# 15_-_PWR_3V3_1V375.net
KiCad netlist of a schematic drawn in Altium Designer
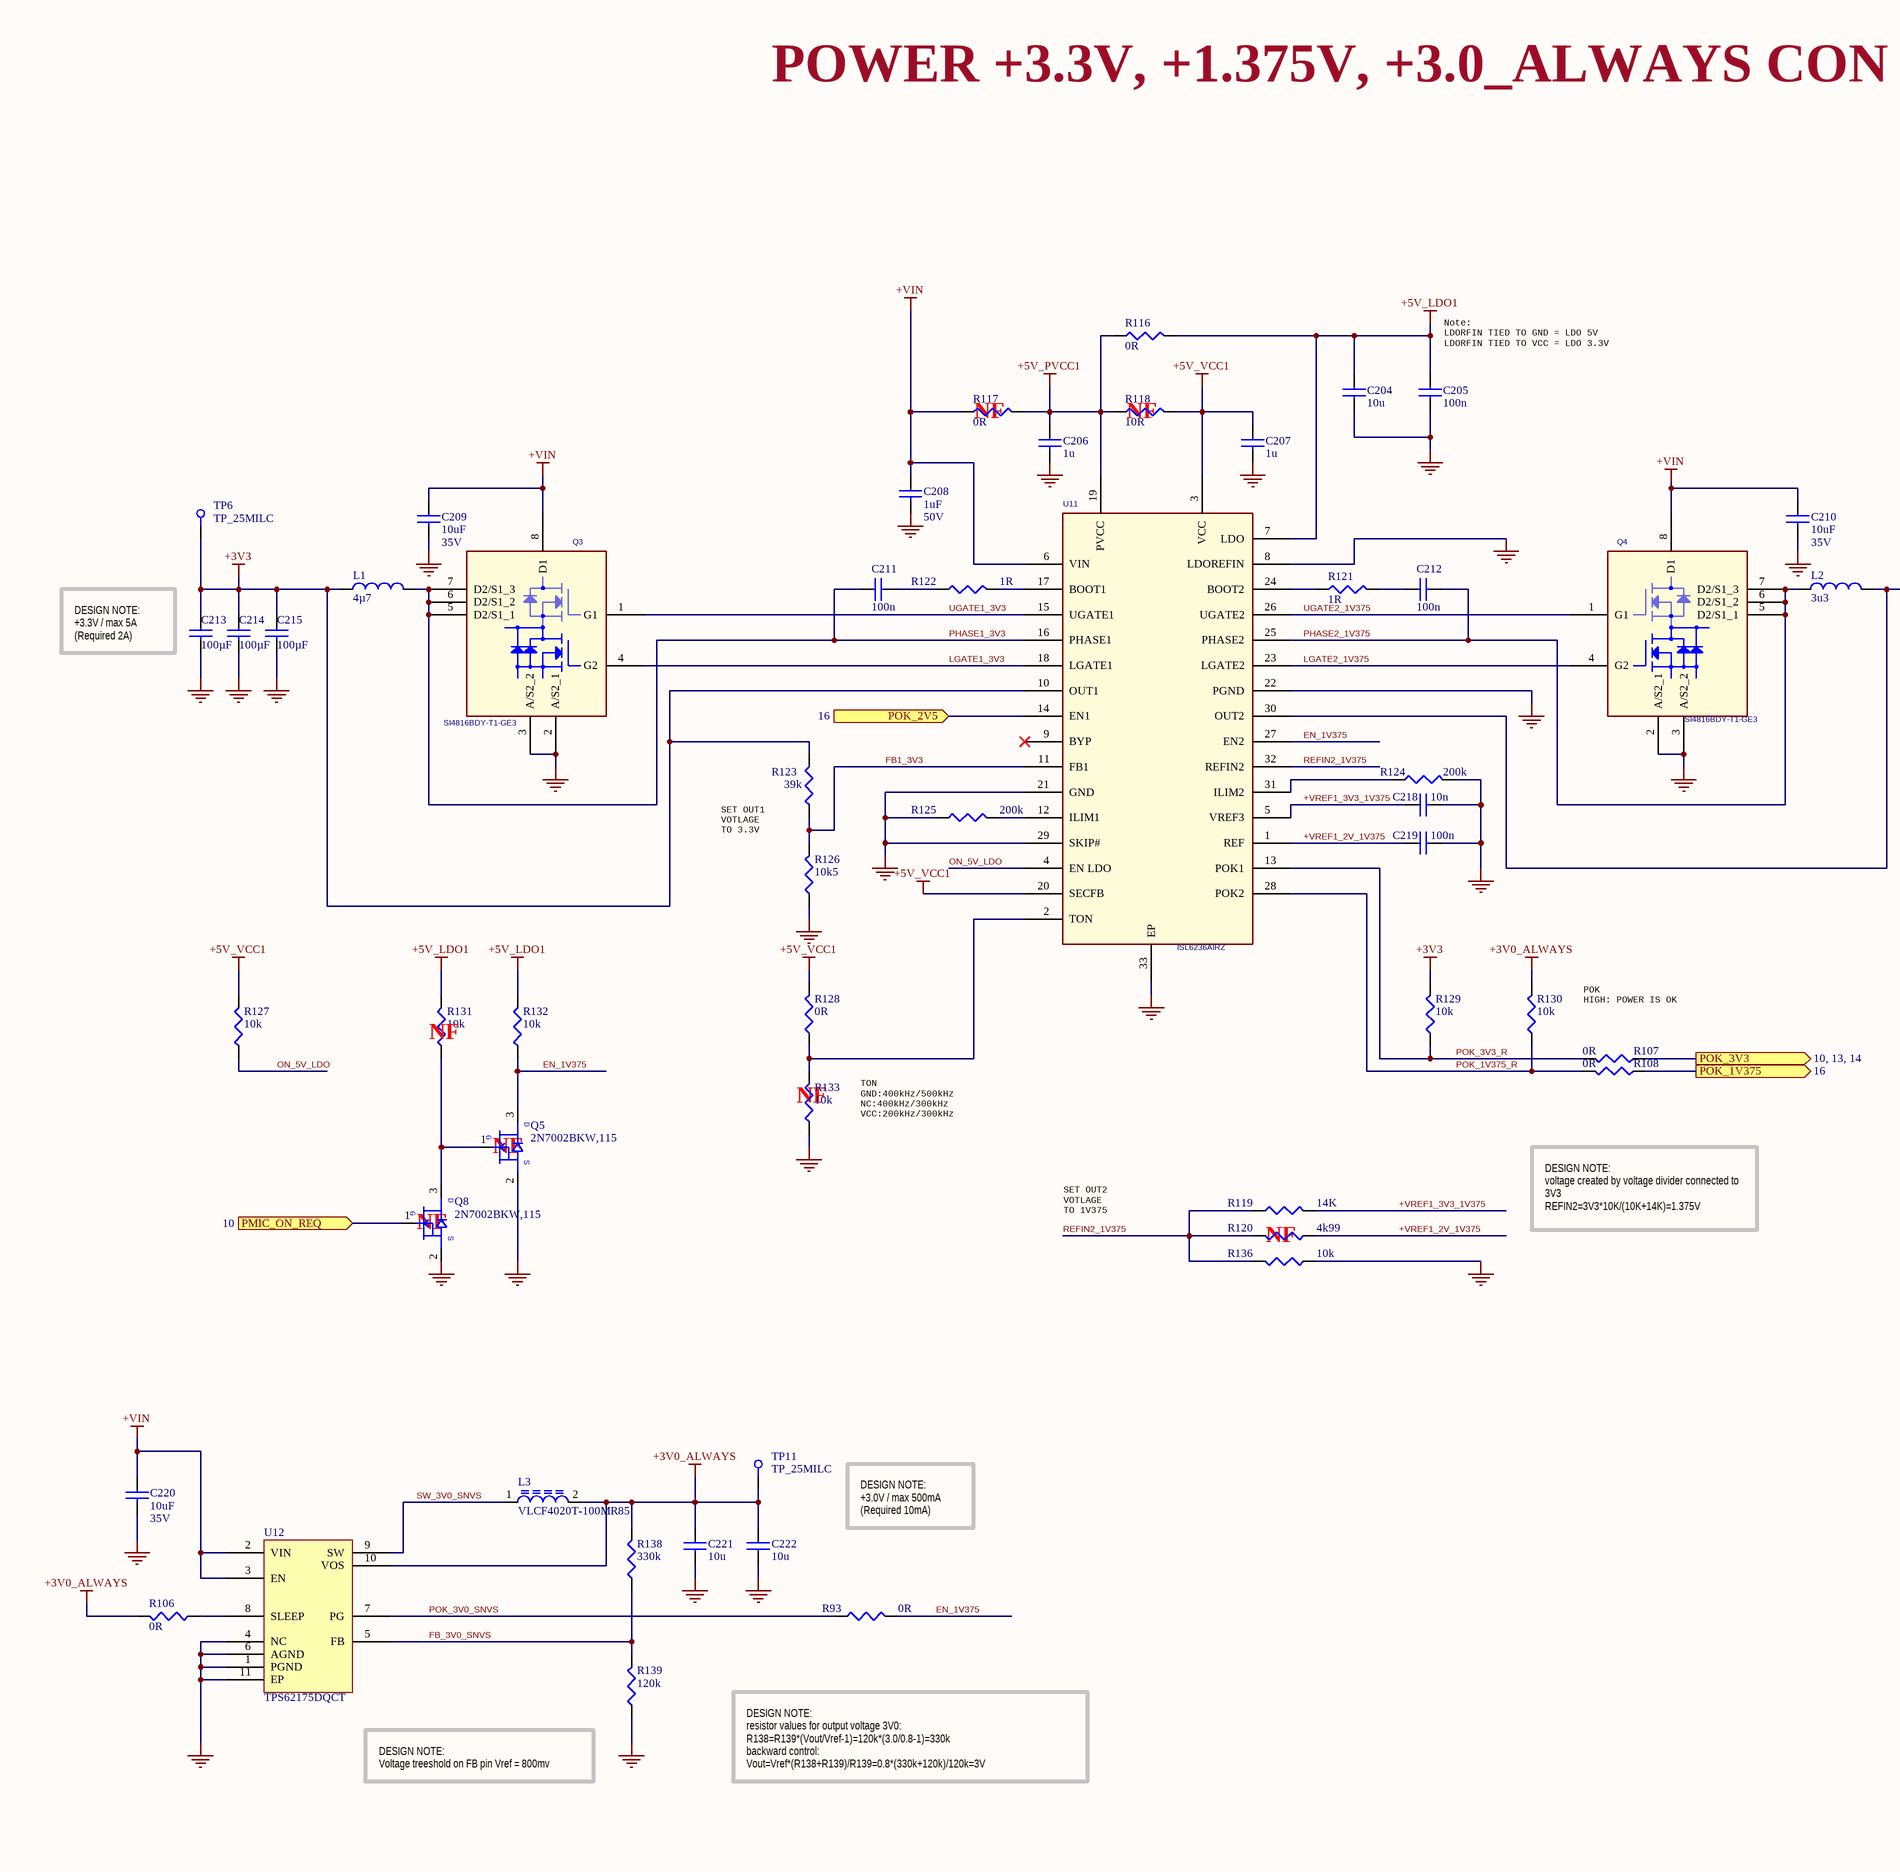
[diagram p0: [15] - PWR 3V3, 1V375.SchDoc, left]
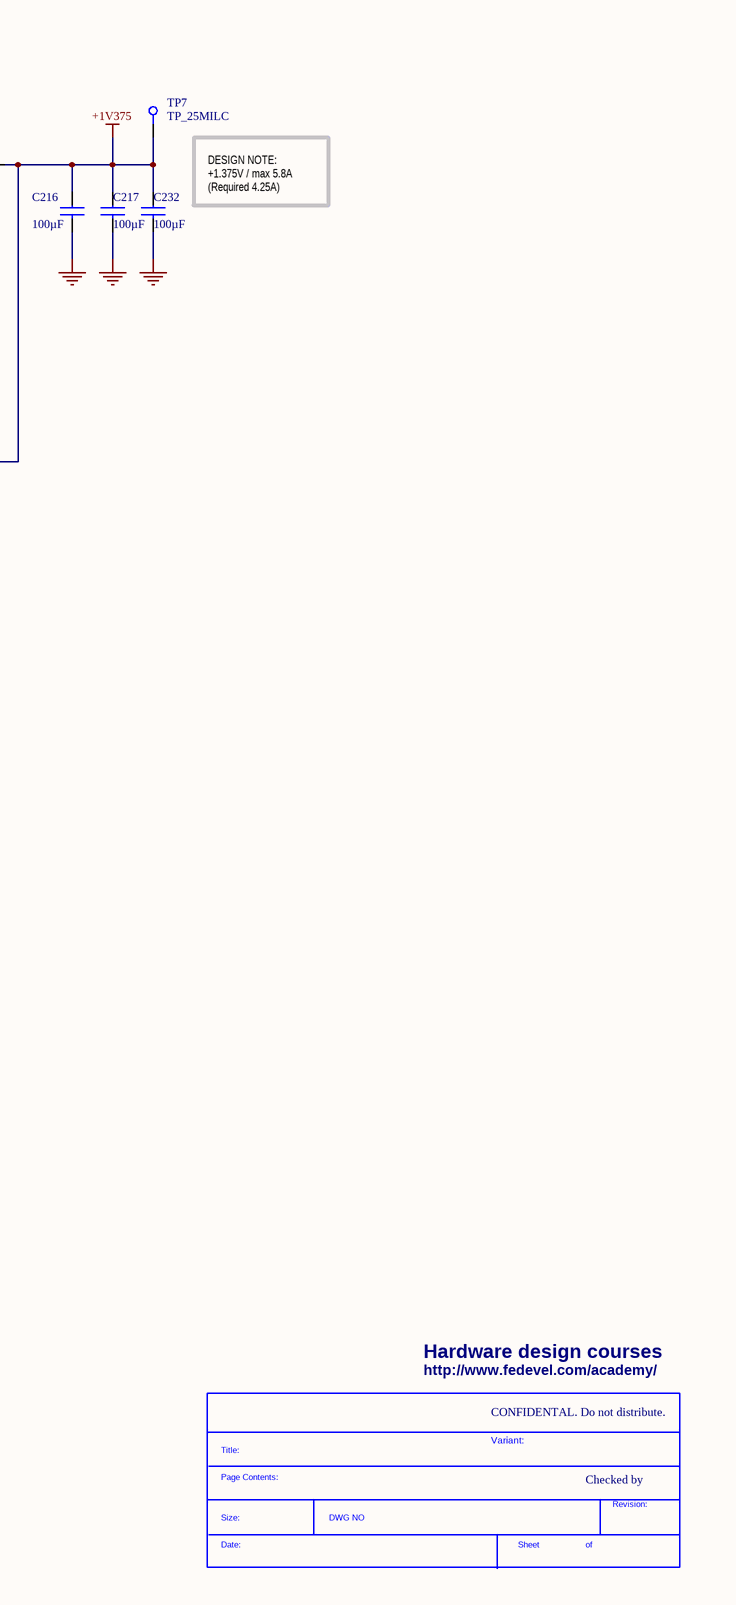
[diagram p1: [15] - PWR 3V3, 1V375.SchDoc, right]

(export (version "E")
  (design (tool "Eeschema 10.0.6"))
  (components
    (comp (ref "C204")
      (value "10u")
      (footprint "C0603")
      (description "CAP CER 10UF 6.3V X5R 20% 0603")
      (fields
        (field (name "MANUFACTURER") "TDK Corporation")
        (field (name "MANUFACTURER PART NUMBER") "C1608X5R0J106M")
      )
      (libsource (lib "Integrated_Library_RF_FEB_2012") (part "C1608X5R0J106M"))
    )
    (comp (ref "C205")
      (value "100n")
      (footprint "C0402")
      (description "CAP CER .10UF 50V X5R 10% 0402")
      (fields
        (field (name "MANUFACTURER") "TDK Corporation")
        (field (name "MANUFACTURER PART NUMBER") "C1005X5R1H104K")
      )
      (libsource (lib "Integrated_Library_RF_FEB_2012") (part "C1005X5R1H104K"))
    )
    (comp (ref "C206")
      (value "1u")
      (footprint "C0402")
      (description "CAP CER 1.0UF 16V X5R 0402")
      (fields
        (field (name "MANUFACTURER") "TDK Corporation")
        (field (name "MANUFACTURER PART NUMBER") "C1005X5R1C105K")
      )
      (libsource (lib "Integrated_Library_RF_FEB_2012") (part "C1005X5R1C105K"))
    )
    (comp (ref "C207")
      (value "1u")
      (footprint "C0402")
      (description "CAP CER 1.0UF 16V X5R 0402")
      (fields
        (field (name "MANUFACTURER") "TDK Corporation")
        (field (name "MANUFACTURER PART NUMBER") "C1005X5R1C105K")
      )
      (libsource (lib "Integrated_Library_RF_FEB_2012") (part "C1005X5R1C105K"))
    )
    (comp (ref "C208")
      (value "1uF")
      (footprint "C0805")
      (description "CAP CER 1UF 50V X7R 0805")
      (fields
        (field (name "MANUFACTURER") "Murata Electronics North America")
        (field (name "MANUFACTURER PART NUMBER") "GRM21BR71H105KA12L")
        (field (name "VOLTAGE - RATED") "50V")
      )
      (libsource (lib "Integrated_Library_RF_FEB_2012") (part "GRM21BR71H105KA12L"))
    )
    (comp (ref "C209")
      (value "10uF")
      (footprint "C1206")
      (description "CAP CER 10UF 35V X5R 1206")
      (fields
        (field (name "MANUFACTURER") "Murata Electronics North America")
        (field (name "MANUFACTURER PART NUMBER") "GRM31CR6YA106KA12L")
        (field (name "VOLTAGE - RATED") "35V")
      )
      (libsource (lib "Integrated_Library_RF_FEB_2012") (part "GRM31CR6YA106KA12L"))
    )
    (comp (ref "C210")
      (value "10uF")
      (footprint "C1206")
      (description "CAP CER 10UF 35V X5R 1206")
      (fields
        (field (name "MANUFACTURER") "Murata Electronics North America")
        (field (name "MANUFACTURER PART NUMBER") "GRM31CR6YA106KA12L")
        (field (name "VOLTAGE - RATED") "35V")
      )
      (libsource (lib "Integrated_Library_RF_FEB_2012") (part "GRM31CR6YA106KA12L"))
    )
    (comp (ref "C211")
      (value "100n")
      (footprint "C0402")
      (description "CAP CER .10UF 50V X5R 10% 0402")
      (fields
        (field (name "MANUFACTURER") "TDK Corporation")
        (field (name "MANUFACTURER PART NUMBER") "C1005X5R1H104K")
      )
      (libsource (lib "Integrated_Library_RF_FEB_2012") (part "C1005X5R1H104K"))
    )
    (comp (ref "C212")
      (value "100n")
      (footprint "C0402")
      (description "CAP CER .10UF 50V X5R 10% 0402")
      (fields
        (field (name "MANUFACTURER") "TDK Corporation")
        (field (name "MANUFACTURER PART NUMBER") "C1005X5R1H104K")
      )
      (libsource (lib "Integrated_Library_RF_FEB_2012") (part "C1005X5R1H104K"))
    )
    (comp (ref "C213")
      (value "100µF")
      (footprint "C1206")
      (description "CAP CER 100UF 10V X5R 20% 1206")
      (fields
        (field (name "MANUFACTURER") "TDK Corporation")
        (field (name "MANUFACTURER PART NUMBER") "C3216X5R1A107M")
      )
      (libsource (lib "Integrated_Library_RF_FEB_2012") (part "C3216X5R1A107M"))
    )
    (comp (ref "C214")
      (value "100µF")
      (footprint "C1206")
      (description "CAP CER 100UF 10V X5R 20% 1206")
      (fields
        (field (name "MANUFACTURER") "TDK Corporation")
        (field (name "MANUFACTURER PART NUMBER") "C3216X5R1A107M")
      )
      (libsource (lib "Integrated_Library_RF_FEB_2012") (part "C3216X5R1A107M"))
    )
    (comp (ref "C215")
      (value "100µF")
      (footprint "C1206")
      (description "CAP CER 100UF 10V X5R 20% 1206")
      (fields
        (field (name "MANUFACTURER") "TDK Corporation")
        (field (name "MANUFACTURER PART NUMBER") "C3216X5R1A107M")
      )
      (libsource (lib "Integrated_Library_RF_FEB_2012") (part "C3216X5R1A107M"))
    )
    (comp (ref "C216")
      (value "100µF")
      (footprint "C1206")
      (description "CAP CER 100UF 10V X5R 20% 1206")
      (fields
        (field (name "MANUFACTURER") "TDK Corporation")
        (field (name "MANUFACTURER PART NUMBER") "C3216X5R1A107M")
      )
      (libsource (lib "Integrated_Library_RF_FEB_2012") (part "C3216X5R1A107M"))
    )
    (comp (ref "C217")
      (value "100µF")
      (footprint "C1206")
      (description "CAP CER 100UF 10V X5R 20% 1206")
      (fields
        (field (name "MANUFACTURER") "TDK Corporation")
        (field (name "MANUFACTURER PART NUMBER") "C3216X5R1A107M")
      )
      (libsource (lib "Integrated_Library_RF_FEB_2012") (part "C3216X5R1A107M"))
    )
    (comp (ref "C218")
      (value "10n")
      (footprint "C0402")
      (description "CAP CER 10000PF 16V X7R 10% 0402")
      (fields
        (field (name "MANUFACTURER") "TDK Corporation")
        (field (name "MANUFACTURER PART NUMBER") "C1005X7R1C103K")
      )
      (libsource (lib "Integrated_Library_RF_FEB_2012") (part "C1005X7R1C103K"))
    )
    (comp (ref "C219")
      (value "100n")
      (footprint "C0402")
      (description "CAP CER .10UF 50V X5R 10% 0402")
      (fields
        (field (name "MANUFACTURER") "TDK Corporation")
        (field (name "MANUFACTURER PART NUMBER") "C1005X5R1H104K")
      )
      (libsource (lib "Integrated_Library_RF_FEB_2012") (part "C1005X5R1H104K"))
    )
    (comp (ref "C220")
      (value "10uF")
      (footprint "C1206")
      (description "CAP CER 10UF 35V X5R 1206")
      (fields
        (field (name "MANUFACTURER") "Murata Electronics North America")
        (field (name "MANUFACTURER PART NUMBER") "GRM31CR6YA106KA12L")
        (field (name "VOLTAGE - RATED") "35V")
      )
      (libsource (lib "Integrated_Library_RF_FEB_2012") (part "GRM31CR6YA106KA12L"))
    )
    (comp (ref "C221")
      (value "10u")
      (footprint "C0603")
      (description "CAP CER 10UF 6.3V X5R 20% 0603")
      (fields
        (field (name "MANUFACTURER") "TDK Corporation")
        (field (name "MANUFACTURER PART NUMBER") "C1608X5R0J106M")
      )
      (libsource (lib "Integrated_Library_RF_FEB_2012") (part "C1608X5R0J106M"))
    )
    (comp (ref "C222")
      (value "10u")
      (footprint "C0603")
      (description "CAP CER 10UF 6.3V X5R 20% 0603")
      (fields
        (field (name "MANUFACTURER") "TDK Corporation")
        (field (name "MANUFACTURER PART NUMBER") "C1608X5R0J106M")
      )
      (libsource (lib "Integrated_Library_RF_FEB_2012") (part "C1608X5R0J106M"))
    )
    (comp (ref "C232")
      (value "100µF")
      (footprint "C1206")
      (description "CAP CER 100UF 10V X5R 20% 1206")
      (fields
        (field (name "MANUFACTURER") "TDK Corporation")
        (field (name "MANUFACTURER PART NUMBER") "C3216X5R1A107M")
      )
      (libsource (lib "Integrated_Library_RF_FEB_2012") (part "C3216X5R1A107M"))
    )
    (comp (ref "L1")
      (value "4µ7")
      (footprint "IHLP_255MILx270MIL")
      (description "INDUCTOR POWER 4.7UH 5.5A SMD")
      (fields
        (field (name "MANUFACTURER") "Vishay/Dale")
        (field (name "MANUFACTURER PART NUMBER") "IHLP2525CZER4R7M01")
      )
      (libsource (lib "Integrated_Library_RF_FEB_2012") (part "IHLP2525CZER4R7M01"))
    )
    (comp (ref "L2")
      (value "3u3")
      (footprint "IHLP_255MILx270MIL")
      (description "INDUCTOR POWER 3.3UH 6A SMD")
      (fields
        (field (name "MANUFACTURER") "Vishay Dale")
        (field (name "MANUFACTURER PART NUMBER") "IHLP2525CZER3R3M01")
        (field (name ".CHECKED PCB") "RF")
        (field (name ".CHECKED SCH") "RF")
      )
      (libsource (lib "Integrated_Library_RF_FEB_2012") (part "IHLP2525CZER3R3M01"))
    )
    (comp (ref "L3")
      (value "VLCF4020T-100MR85")
      (footprint "VLCF4020")
      (description "INDUCTOR POWER 10UH .85A SMD")
      (fields
        (field (name "MANUFACTURER") "TDK Corporation")
        (field (name "TOLERANCE") "±20%")
        (field (name ".CREATOR") "MM")
        (field (name ".CHECKED PCB") "MM, checked by RF")
        (field (name ".CHECKED SCH") "MM, checked by RF")
      )
      (libsource (lib "Schlib_RF") (part "VLCF4020T-100MR85"))
    )
    (comp (ref "Q3")
      (value "SI4816BDY-T1-GE3")
      (footprint "8_SOIC_3.9MM")
      (description "MOSFET DL N-CH 30V 6.8A 8-SOIC")
      (fields (field (name "MANUFACTURER") "Vishay/Siliconix"))
      (libsource (lib "Integrated_Library_RF_FEB_2012") (part "SI4816BDY-T1-GE3"))
    )
    (comp (ref "Q4")
      (value "SI4816BDY-T1-GE3")
      (footprint "8_SOIC_3.9MM")
      (description "MOSFET DL N-CH 30V 6.8A 8-SOIC")
      (fields (field (name "MANUFACTURER") "Vishay/Siliconix"))
      (libsource (lib "Integrated_Library_RF_FEB_2012") (part "SI4816BDY-T1-GE3"))
    )
    (comp (ref "Q5")
      (value "2N7002BKW,115")
      (footprint "SC70_SOT323")
      (description "MOSFET N-CH 60V 310MA SOT323")
      (fields
        (field (name "MANUFACTURER") "NXP Semiconductors")
        (field (name ".CHECKED PCB") "RF")
        (field (name ".CHECKED SCH") "RF")
      )
      (libsource (lib "Integrated_Library_RF_FEB_2012") (part "2N7002BKW,115"))
    )
    (comp (ref "Q8")
      (value "2N7002BKW,115")
      (footprint "SC70_SOT323")
      (description "MOSFET N-CH 60V 310MA SOT323")
      (fields
        (field (name "MANUFACTURER") "NXP Semiconductors")
        (field (name ".CHECKED PCB") "RF")
        (field (name ".CHECKED SCH") "RF")
      )
      (libsource (lib "Integrated_Library_RF_FEB_2012") (part "2N7002BKW,115"))
    )
    (comp (ref "R93")
      (value "0R")
      (footprint "R0402")
      (description "RES 0.0 OHM 1/16W 0402 SMD")
      (fields
        (field (name "MANUFACTURER") "Yageo")
        (field (name "MANUFACTURER PART NUMBER") "RC0402JR-070RL")
      )
      (libsource (lib "Integrated_Library_RF_FEB_2012") (part "RC0402JR-070RL"))
    )
    (comp (ref "R106")
      (value "0R")
      (footprint "R0402")
      (description "RES 0.0 OHM 1/16W 0402 SMD")
      (fields
        (field (name "MANUFACTURER") "Yageo")
        (field (name "MANUFACTURER PART NUMBER") "RC0402JR-070RL")
      )
      (libsource (lib "Integrated_Library_RF_FEB_2012") (part "RC0402JR-070RL"))
    )
    (comp (ref "R107")
      (value "0R")
      (footprint "R0402")
      (description "RES 0.0 OHM 1/16W 0402 SMD")
      (fields
        (field (name "MANUFACTURER") "Yageo")
        (field (name "MANUFACTURER PART NUMBER") "RC0402JR-070RL")
      )
      (libsource (lib "Integrated_Library_RF_FEB_2012") (part "RC0402JR-070RL"))
    )
    (comp (ref "R108")
      (value "0R")
      (footprint "R0402")
      (description "RES 0.0 OHM 1/16W 0402 SMD")
      (fields
        (field (name "MANUFACTURER") "Yageo")
        (field (name "MANUFACTURER PART NUMBER") "RC0402JR-070RL")
      )
      (libsource (lib "Integrated_Library_RF_FEB_2012") (part "RC0402JR-070RL"))
    )
    (comp (ref "R116")
      (value "0R")
      (footprint "R0402")
      (description "RES 0.0 OHM 1/16W 0402 SMD")
      (fields
        (field (name "MANUFACTURER") "Yageo")
        (field (name "MANUFACTURER PART NUMBER") "RC0402JR-070RL")
      )
      (libsource (lib "Integrated_Library_RF_FEB_2012") (part "RC0402JR-070RL"))
    )
    (comp (ref "R117")
      (value "0R")
      (footprint "R0402")
      (description "RES 0.0 OHM 1/16W 0402 SMD")
      (fields
        (field (name "MANUFACTURER") "Yageo")
        (field (name "MANUFACTURER PART NUMBER") "RC0402JR-070RL")
      )
      (libsource (lib "Integrated_Library_RF_FEB_2012") (part "RC0402JR-070RL"))
    )
    (comp (ref "R118")
      (value "10R")
      (footprint "R0402")
      (description "RES 10.0 OHM 1/16W 1% 0402 SMD")
      (fields
        (field (name "MANUFACTURER") "Yageo")
        (field (name "MANUFACTURER PART NUMBER") "RC0402FR-0710RL")
      )
      (libsource (lib "Integrated_Library_RF_FEB_2012") (part "RC0402FR-0710RL"))
    )
    (comp (ref "R119")
      (value "14K")
      (footprint "R0402")
      (description "RES 14.0K OHM 1/16W 1% 0402 SMD")
      (fields
        (field (name "MANUFACTURER") "Yageo")
        (field (name "MANUFACTURER PART NUMBER") "RC0402FR-0714KL")
        (field (name "CREATOR") "MM")
        (field (name ".CHECKED PCB") "RF, used by MM")
        (field (name ".CHECKED SCH") "MM, checked by RF")
        (field (name ".CREATOR") "MM")
      )
      (libsource (lib "Schlib_RF") (part "RC0402FR-0714KL"))
    )
    (comp (ref "R120")
      (value "4k99")
      (footprint "R0402")
      (description "RES TF 4.99K OHM 1% 1/16W 0402")
      (fields
        (field (name "MANUFACTURER") "Stackpole Electronics Inc")
        (field (name "MANUFACTURER PART NUMBER") "RMCF0402FT4K99")
      )
      (libsource (lib "Integrated_Library_RF_FEB_2012") (part "RMCF0402FT4K99"))
    )
    (comp (ref "R121")
      (value "1R")
      (footprint "R0402")
      (description "RES 1.00 OHM 1/16W 1% 0402 SM")
      (fields
        (field (name "MANUFACTURER") "Yageo")
        (field (name "MANUFACTURER PART NUMBER") "RC0402FR-071RL")
      )
      (libsource (lib "Integrated_Library_RF_FEB_2012") (part "RC0402FR-071RL"))
    )
    (comp (ref "R122")
      (value "1R")
      (footprint "R0402")
      (description "RES 1.00 OHM 1/16W 1% 0402 SM")
      (fields
        (field (name "MANUFACTURER") "Yageo")
        (field (name "MANUFACTURER PART NUMBER") "RC0402FR-071RL")
      )
      (libsource (lib "Integrated_Library_RF_FEB_2012") (part "RC0402FR-071RL"))
    )
    (comp (ref "R123")
      (value "39k")
      (footprint "R0402")
      (description "RES 39.0K OHM 1/16W 1% 0402 SMD")
      (fields
        (field (name "MANUFACTURER") "Yageo")
        (field (name "MANUFACTURER PART NUMBER") "RC0402FR-0739KL")
      )
      (libsource (lib "Integrated_Library_RF_FEB_2012") (part "RC0402FR-0739KL"))
    )
    (comp (ref "R124")
      (value "200k")
      (footprint "R0402")
      (description "RES 200K OHM 1/16W 1% 0402 SMD")
      (fields
        (field (name "MANUFACTURER") "Yageo")
        (field (name "MANUFACTURER PART NUMBER") "RC0402FR-07200KL")
      )
      (libsource (lib "Integrated_Library_RF_FEB_2012") (part "RC0402FR-07200KL"))
    )
    (comp (ref "R125")
      (value "200k")
      (footprint "R0402")
      (description "RES 200K OHM 1/16W 1% 0402 SMD")
      (fields
        (field (name "MANUFACTURER") "Yageo")
        (field (name "MANUFACTURER PART NUMBER") "RC0402FR-07200KL")
      )
      (libsource (lib "Integrated_Library_RF_FEB_2012") (part "RC0402FR-07200KL"))
    )
    (comp (ref "R126")
      (value "10k5")
      (footprint "R0402")
      (description "RES 10.5K OHM 1/16W 1% 0402 SMD")
      (fields
        (field (name "MANUFACTURER") "Vishay/Dale")
        (field (name "MANUFACTURER PART NUMBER") "CRCW040210K5FKED")
      )
      (libsource (lib "Integrated_Library_RF_FEB_2012") (part "CRCW040210K5FKED"))
    )
    (comp (ref "R127")
      (value "10k")
      (footprint "R0402")
      (description "RES 10.0K OHM 1/16W 1% 0402 SMD")
      (fields
        (field (name "MANUFACTURER") "Yageo")
        (field (name "MANUFACTURER PART NUMBER") "RC0402FR-0710KL")
      )
      (libsource (lib "Integrated_Library_RF_FEB_2012") (part "RC0402FR-0710KL"))
    )
    (comp (ref "R128")
      (value "0R")
      (footprint "R0402")
      (description "RES 0.0 OHM 1/16W 0402 SMD")
      (fields
        (field (name "MANUFACTURER") "Yageo")
        (field (name "MANUFACTURER PART NUMBER") "RC0402JR-070RL")
      )
      (libsource (lib "Integrated_Library_RF_FEB_2012") (part "RC0402JR-070RL"))
    )
    (comp (ref "R129")
      (value "10k")
      (footprint "R0402")
      (description "RES 10.0K OHM 1/16W 1% 0402 SMD")
      (fields
        (field (name "MANUFACTURER") "Yageo")
        (field (name "MANUFACTURER PART NUMBER") "RC0402FR-0710KL")
      )
      (libsource (lib "Integrated_Library_RF_FEB_2012") (part "RC0402FR-0710KL"))
    )
    (comp (ref "R130")
      (value "10k")
      (footprint "R0402")
      (description "RES 10.0K OHM 1/16W 1% 0402 SMD")
      (fields
        (field (name "MANUFACTURER") "Yageo")
        (field (name "MANUFACTURER PART NUMBER") "RC0402FR-0710KL")
      )
      (libsource (lib "Integrated_Library_RF_FEB_2012") (part "RC0402FR-0710KL"))
    )
    (comp (ref "R131")
      (value "10k")
      (footprint "R0402")
      (description "RES 10.0K OHM 1/16W 1% 0402 SMD")
      (fields
        (field (name "MANUFACTURER") "Yageo")
        (field (name "MANUFACTURER PART NUMBER") "RC0402FR-0710KL")
      )
      (libsource (lib "Integrated_Library_RF_FEB_2012") (part "RC0402FR-0710KL"))
    )
    (comp (ref "R132")
      (value "10k")
      (footprint "R0402")
      (description "RES 10.0K OHM 1/16W 1% 0402 SMD")
      (fields
        (field (name "MANUFACTURER") "Yageo")
        (field (name "MANUFACTURER PART NUMBER") "RC0402FR-0710KL")
      )
      (libsource (lib "Integrated_Library_RF_FEB_2012") (part "RC0402FR-0710KL"))
    )
    (comp (ref "R133")
      (value "10k")
      (footprint "R0402")
      (description "RES 10.0K OHM 1/16W 1% 0402 SMD")
      (fields
        (field (name "MANUFACTURER") "Yageo")
        (field (name "MANUFACTURER PART NUMBER") "RC0402FR-0710KL")
      )
      (libsource (lib "Integrated_Library_RF_FEB_2012") (part "RC0402FR-0710KL"))
    )
    (comp (ref "R136")
      (value "10k")
      (footprint "R0402")
      (description "RES 10.0K OHM 1/16W 1% 0402 SMD")
      (fields
        (field (name "MANUFACTURER") "Yageo")
        (field (name "MANUFACTURER PART NUMBER") "RC0402FR-0710KL")
      )
      (libsource (lib "Integrated_Library_RF_FEB_2012") (part "RC0402FR-0710KL"))
    )
    (comp (ref "R138")
      (value "330k")
      (footprint "R0402")
      (description "RES 330K OHM 1/16W 1% 0402 SMD")
      (fields
        (field (name "MANUFACTURER") "Vishay Dale")
        (field (name "MANUFACTURER PART NUMBER") "CRCW0402330KFKED")
        (field (name ".CHECKED PCB") "RF")
        (field (name ".CHECKED SCH") "RF")
      )
      (libsource (lib "Integrated_Library_RF_FEB_2012") (part "CRCW0402330KFKED"))
    )
    (comp (ref "R139")
      (value "120k")
      (footprint "R0402")
      (description "RES 120K OHM 1/16W 1% 0402 SMD")
      (fields
        (field (name "MANUFACTURER") "Yageo")
        (field (name "MANUFACTURER PART NUMBER") "RC0402FR-07120KL")
        (field (name ".CHECKED PCB") "OK RF")
        (field (name ".CHECKED SCH") "RF")
      )
      (libsource (lib "Integrated_Library_RF_FEB_2012") (part "RC0402FR-07120KL"))
    )
    (comp (ref "TP6")
      (value "TP_25MILC")
      (footprint "TP_25C")
      (description "Test Point 25mil")
      (libsource (lib "Integrated_Library_RF_FEB_2012") (part "TP_25MILC"))
    )
    (comp (ref "TP7")
      (value "TP_25MILC")
      (footprint "TP_25C")
      (description "Test Point 25mil")
      (libsource (lib "Integrated_Library_RF_FEB_2012") (part "TP_25MILC"))
    )
    (comp (ref "TP11")
      (value "TP_25MILC")
      (footprint "TP_25C")
      (description "Test Point 25mil")
      (libsource (lib "Integrated_Library_RF_FEB_2012") (part "TP_25MILC"))
    )
    (comp (ref "U11")
      (value "ISL6236AIRZ")
      (footprint "32_VFQFN_EXPOSED_PAD")
      (description "IC MAIN PWR CTRLR QUAD 32-QFN")
      (fields (field (name "MANUFACTURER") "Intersil"))
      (libsource (lib "Integrated_Library_RF_FEB_2012") (part "ISL6236AIRZ"))
    )
    (comp (ref "U12")
      (value "TPS62175DQCT")
      (footprint "DQC_PWSON-N10")
      (description "IC REG BUCK SYNC ADJ 0.5A 10WSON")
      (fields
        (field (name "MANUFACTURER") "Texas Instruments")
        (field (name ".CREATOR") "MM")
        (field (name ".CHECKED PCB") "MM, checked by RF")
        (field (name ".CHECKED SCH") "MM, checked by RF")
      )
      (libsource (lib "Schlib_RF") (part "TPS62175DQCT"))
    )
  )
  (nets
    (net (code "1") (name "+1V375") (class "Default")
      (node (ref "C216") (pin "1") (pinfunction "1_1") (pintype "passive"))
      (node (ref "C217") (pin "1") (pinfunction "1_1") (pintype "passive"))
      (node (ref "C232") (pin "1") (pinfunction "1_1") (pintype "passive"))
      (node (ref "L2") (pin "2") (pinfunction "2_2") (pintype "passive"))
      (node (ref "TP7") (pin "1") (pinfunction "1_1") (pintype "passive"))
      (node (ref "U11") (pin "30") (pinfunction "OUT2_30") (pintype "passive"))
    )
    (net (code "2") (name "+3V0_ALWAYS") (class "Default")
      (node (ref "C221") (pin "1") (pinfunction "1_1") (pintype "passive"))
      (node (ref "C222") (pin "1") (pinfunction "1_1") (pintype "passive"))
      (node (ref "L3") (pin "2") (pinfunction "2_2") (pintype "passive"))
      (node (ref "R106") (pin "2") (pinfunction "2_2") (pintype "passive"))
      (node (ref "R130") (pin "2") (pinfunction "2_2") (pintype "passive"))
      (node (ref "R138") (pin "2") (pinfunction "2_2") (pintype "passive"))
      (node (ref "TP11") (pin "1") (pinfunction "1_1") (pintype "passive"))
      (node (ref "U12") (pin "10") (pinfunction "VOS_10") (pintype "passive"))
    )
    (net (code "3") (name "+3V3") (class "Default")
      (node (ref "C213") (pin "1") (pinfunction "1_1") (pintype "passive"))
      (node (ref "C214") (pin "1") (pinfunction "1_1") (pintype "passive"))
      (node (ref "C215") (pin "1") (pinfunction "1_1") (pintype "passive"))
      (node (ref "L1") (pin "1") (pinfunction "1_1") (pintype "passive"))
      (node (ref "R123") (pin "2") (pinfunction "2_2") (pintype "passive"))
      (node (ref "R129") (pin "2") (pinfunction "2_2") (pintype "passive"))
      (node (ref "TP6") (pin "1") (pinfunction "1_1") (pintype "passive"))
      (node (ref "U11") (pin "10") (pinfunction "OUT1_10") (pintype "passive"))
    )
    (net (code "4") (name "+5V_LDO1") (class "Default")
      (node (ref "C204") (pin "1") (pinfunction "1_1") (pintype "passive"))
      (node (ref "C205") (pin "1") (pinfunction "1_1") (pintype "passive"))
      (node (ref "R116") (pin "2") (pinfunction "2_2") (pintype "passive"))
      (node (ref "R131") (pin "2") (pinfunction "2_2") (pintype "passive"))
      (node (ref "R132") (pin "2") (pinfunction "2_2") (pintype "passive"))
      (node (ref "U11") (pin "7") (pinfunction "LDO_7") (pintype "passive"))
    )
    (net (code "5") (name "+5V_PVCC1") (class "Default")
      (node (ref "C206") (pin "1") (pinfunction "1_1") (pintype "passive"))
      (node (ref "R116") (pin "1") (pinfunction "1_1") (pintype "passive"))
      (node (ref "R117") (pin "2") (pinfunction "2_2") (pintype "passive"))
      (node (ref "R118") (pin "1") (pinfunction "1_1") (pintype "passive"))
      (node (ref "U11") (pin "19") (pinfunction "PVCC_19") (pintype "passive"))
    )
    (net (code "6") (name "+5V_VCC1") (class "Default")
      (node (ref "C207") (pin "1") (pinfunction "1_1") (pintype "passive"))
      (node (ref "R118") (pin "2") (pinfunction "2_2") (pintype "passive"))
      (node (ref "R127") (pin "2") (pinfunction "2_2") (pintype "passive"))
      (node (ref "R128") (pin "2") (pinfunction "2_2") (pintype "passive"))
      (node (ref "U11") (pin "20") (pinfunction "SECFB_20") (pintype "passive"))
      (node (ref "U11") (pin "3") (pinfunction "VCC_3") (pintype "passive"))
    )
    (net (code "7") (name "+VIN") (class "Default")
      (node (ref "C208") (pin "1") (pinfunction "1_1") (pintype "passive"))
      (node (ref "C209") (pin "1") (pinfunction "1_1") (pintype "passive"))
      (node (ref "C210") (pin "1") (pinfunction "1_1") (pintype "passive"))
      (node (ref "C220") (pin "1") (pinfunction "1_1") (pintype "passive"))
      (node (ref "Q3") (pin "8") (pinfunction "D1_8") (pintype "passive"))
      (node (ref "Q4") (pin "8") (pinfunction "D1_8") (pintype "passive"))
      (node (ref "R117") (pin "1") (pinfunction "1_1") (pintype "passive"))
      (node (ref "U11") (pin "6") (pinfunction "VIN_6") (pintype "passive"))
      (node (ref "U12") (pin "2") (pinfunction "VIN_2") (pintype "passive"))
      (node (ref "U12") (pin "3") (pinfunction "EN_3") (pintype "passive"))
    )
    (net (code "8") (name "/+VREF1_2V_1V375") (class "Default")
      (node (ref "C219") (pin "1") (pinfunction "1_1") (pintype "passive"))
      (node (ref "R120") (pin "1") (pinfunction "1_1") (pintype "passive"))
      (node (ref "U11") (pin "1") (pinfunction "REF_1") (pintype "passive"))
    )
    (net (code "9") (name "/+VREF1_3V3_1V375") (class "Default")
      (node (ref "C218") (pin "1") (pinfunction "1_1") (pintype "passive"))
      (node (ref "R119") (pin "2") (pinfunction "2_2") (pintype "passive"))
      (node (ref "U11") (pin "5") (pinfunction "VREF3_5") (pintype "passive"))
    )
    (net (code "10") (name "/EN_1V375") (class "Default")
      (node (ref "Q5") (pin "3") (pinfunction "DRAIN_3") (pintype "passive"))
      (node (ref "R132") (pin "1") (pinfunction "1_1") (pintype "passive"))
      (node (ref "R93") (pin "2") (pinfunction "2_2") (pintype "passive"))
      (node (ref "U11") (pin "27") (pinfunction "EN2_27") (pintype "passive"))
    )
    (net (code "11") (name "/FB1_3V3") (class "Default")
      (node (ref "R123") (pin "1") (pinfunction "1_1") (pintype "passive"))
      (node (ref "R126") (pin "2") (pinfunction "2_2") (pintype "passive"))
      (node (ref "U11") (pin "11") (pinfunction "FB1_11") (pintype "passive"))
    )
    (net (code "12") (name "/FB_3V0_SNVS") (class "Default")
      (node (ref "R138") (pin "1") (pinfunction "1_1") (pintype "passive"))
      (node (ref "R139") (pin "2") (pinfunction "2_2") (pintype "passive"))
      (node (ref "U12") (pin "5") (pinfunction "FB_5") (pintype "passive"))
    )
    (net (code "13") (name "/LGATE1_3V3") (class "Default")
      (node (ref "Q3") (pin "4") (pinfunction "G2_4") (pintype "passive"))
      (node (ref "U11") (pin "18") (pinfunction "LGATE1_18") (pintype "passive"))
    )
    (net (code "14") (name "/LGATE2_1V375") (class "Default")
      (node (ref "Q4") (pin "4") (pinfunction "G2_4") (pintype "passive"))
      (node (ref "U11") (pin "23") (pinfunction "LGATE2_23") (pintype "passive"))
    )
    (net (code "15") (name "/ON_5V_LDO") (class "Default")
      (node (ref "R127") (pin "1") (pinfunction "1_1") (pintype "passive"))
      (node (ref "U11") (pin "4") (pinfunction "EN_LDO_4") (pintype "passive"))
    )
    (net (code "16") (name "/PHASE1_3V3") (class "Default")
      (node (ref "C211") (pin "1") (pinfunction "1_1") (pintype "passive"))
      (node (ref "L1") (pin "2") (pinfunction "2_2") (pintype "passive"))
      (node (ref "Q3") (pin "5") (pinfunction "D2/S1_1_5") (pintype "passive"))
      (node (ref "Q3") (pin "6") (pinfunction "D2/S1_2_6") (pintype "passive"))
      (node (ref "Q3") (pin "7") (pinfunction "D2/S1_3_7") (pintype "passive"))
      (node (ref "U11") (pin "16") (pinfunction "PHASE1_16") (pintype "passive"))
    )
    (net (code "17") (name "/PHASE2_1V375") (class "Default")
      (node (ref "C212") (pin "2") (pinfunction "2_2") (pintype "passive"))
      (node (ref "L2") (pin "1") (pinfunction "1_1") (pintype "passive"))
      (node (ref "Q4") (pin "5") (pinfunction "D2/S1_1_5") (pintype "passive"))
      (node (ref "Q4") (pin "6") (pinfunction "D2/S1_2_6") (pintype "passive"))
      (node (ref "Q4") (pin "7") (pinfunction "D2/S1_3_7") (pintype "passive"))
      (node (ref "U11") (pin "25") (pinfunction "PHASE2_25") (pintype "passive"))
    )
    (net (code "18") (name "/PMIC_ON_REQ") (class "Default")
      (node (ref "Q8") (pin "1") (pinfunction "GATE_1") (pintype "passive"))
    )
    (net (code "19") (name "/POK_1V375") (class "Default")
      (node (ref "R108") (pin "1") (pinfunction "1_1") (pintype "passive"))
    )
    (net (code "20") (name "/POK_1V375_R") (class "Default")
      (node (ref "R108") (pin "2") (pinfunction "2_2") (pintype "passive"))
      (node (ref "R130") (pin "1") (pinfunction "1_1") (pintype "passive"))
      (node (ref "U11") (pin "28") (pinfunction "POK2_28") (pintype "passive"))
    )
    (net (code "21") (name "/POK_2V5") (class "Default")
      (node (ref "U11") (pin "14") (pinfunction "EN1_14") (pintype "passive"))
    )
    (net (code "22") (name "/POK_3V0_SNVS") (class "Default")
      (node (ref "R93") (pin "1") (pinfunction "1_1") (pintype "passive"))
      (node (ref "U12") (pin "7") (pinfunction "PG_7") (pintype "passive"))
    )
    (net (code "23") (name "/POK_3V3") (class "Default")
      (node (ref "R107") (pin "1") (pinfunction "1_1") (pintype "passive"))
    )
    (net (code "24") (name "/POK_3V3_R") (class "Default")
      (node (ref "R107") (pin "2") (pinfunction "2_2") (pintype "passive"))
      (node (ref "R129") (pin "1") (pinfunction "1_1") (pintype "passive"))
      (node (ref "U11") (pin "13") (pinfunction "POK1_13") (pintype "passive"))
    )
    (net (code "25") (name "/REFIN2_1V375") (class "Default")
      (node (ref "R119") (pin "1") (pinfunction "1_1") (pintype "passive"))
      (node (ref "R120") (pin "2") (pinfunction "2_2") (pintype "passive"))
      (node (ref "R136") (pin "2") (pinfunction "2_2") (pintype "passive"))
      (node (ref "U11") (pin "32") (pinfunction "REFIN2_32") (pintype "passive"))
    )
    (net (code "26") (name "/SW_3V0_SNVS") (class "Default")
      (node (ref "L3") (pin "1") (pinfunction "1_1") (pintype "passive"))
      (node (ref "U12") (pin "9") (pinfunction "SW_9") (pintype "passive"))
    )
    (net (code "27") (name "/UGATE1_3V3") (class "Default")
      (node (ref "Q3") (pin "1") (pinfunction "G1_1") (pintype "passive"))
      (node (ref "U11") (pin "15") (pinfunction "UGATE1_15") (pintype "passive"))
    )
    (net (code "28") (name "/UGATE2_1V375") (class "Default")
      (node (ref "Q4") (pin "1") (pinfunction "G1_1") (pintype "passive"))
      (node (ref "U11") (pin "26") (pinfunction "UGATE2_26") (pintype "passive"))
    )
    (net (code "29") (name "GND") (class "Default")
      (node (ref "C204") (pin "2") (pinfunction "2_2") (pintype "passive"))
      (node (ref "C205") (pin "2") (pinfunction "2_2") (pintype "passive"))
      (node (ref "C206") (pin "2") (pinfunction "2_2") (pintype "passive"))
      (node (ref "C207") (pin "2") (pinfunction "2_2") (pintype "passive"))
      (node (ref "C208") (pin "2") (pinfunction "2_2") (pintype "passive"))
      (node (ref "C209") (pin "2") (pinfunction "2_2") (pintype "passive"))
      (node (ref "C210") (pin "2") (pinfunction "2_2") (pintype "passive"))
      (node (ref "C213") (pin "2") (pinfunction "2_2") (pintype "passive"))
      (node (ref "C214") (pin "2") (pinfunction "2_2") (pintype "passive"))
      (node (ref "C215") (pin "2") (pinfunction "2_2") (pintype "passive"))
      (node (ref "C216") (pin "2") (pinfunction "2_2") (pintype "passive"))
      (node (ref "C217") (pin "2") (pinfunction "2_2") (pintype "passive"))
      (node (ref "C218") (pin "2") (pinfunction "2_2") (pintype "passive"))
      (node (ref "C219") (pin "2") (pinfunction "2_2") (pintype "passive"))
      (node (ref "C220") (pin "2") (pinfunction "2_2") (pintype "passive"))
      (node (ref "C221") (pin "2") (pinfunction "2_2") (pintype "passive"))
      (node (ref "C222") (pin "2") (pinfunction "2_2") (pintype "passive"))
      (node (ref "C232") (pin "2") (pinfunction "2_2") (pintype "passive"))
      (node (ref "Q3") (pin "2") (pinfunction "A/S2_1_2") (pintype "passive"))
      (node (ref "Q3") (pin "3") (pinfunction "A/S2_2_3") (pintype "passive"))
      (node (ref "Q4") (pin "2") (pinfunction "A/S2_1_2") (pintype "passive"))
      (node (ref "Q4") (pin "3") (pinfunction "A/S2_2_3") (pintype "passive"))
      (node (ref "Q5") (pin "2") (pinfunction "SOURCE_2") (pintype "passive"))
      (node (ref "Q8") (pin "2") (pinfunction "SOURCE_2") (pintype "passive"))
      (node (ref "R124") (pin "2") (pinfunction "2_2") (pintype "passive"))
      (node (ref "R125") (pin "1") (pinfunction "1_1") (pintype "passive"))
      (node (ref "R126") (pin "1") (pinfunction "1_1") (pintype "passive"))
      (node (ref "R133") (pin "1") (pinfunction "1_1") (pintype "passive"))
      (node (ref "R136") (pin "1") (pinfunction "1_1") (pintype "passive"))
      (node (ref "R139") (pin "1") (pinfunction "1_1") (pintype "passive"))
      (node (ref "U11") (pin "21") (pinfunction "GND_21") (pintype "passive"))
      (node (ref "U11") (pin "22") (pinfunction "PGND_22") (pintype "passive"))
      (node (ref "U11") (pin "29") (pinfunction "SKIP#_29") (pintype "passive"))
      (node (ref "U11") (pin "33") (pinfunction "EP_33") (pintype "passive"))
      (node (ref "U11") (pin "8") (pinfunction "LDOREFIN_8") (pintype "passive"))
      (node (ref "U12") (pin "1") (pinfunction "PGND_1") (pintype "passive"))
      (node (ref "U12") (pin "11") (pinfunction "EP_11") (pintype "passive"))
      (node (ref "U12") (pin "4") (pinfunction "NC_4") (pintype "passive"))
      (node (ref "U12") (pin "6") (pinfunction "AGND_6") (pintype "passive"))
    )
    (net (code "30") (name "Net-(C211-Pad2)") (class "Default")
      (node (ref "C211") (pin "2") (pinfunction "2_2") (pintype "passive"))
      (node (ref "R122") (pin "1") (pinfunction "1_1") (pintype "passive"))
    )
    (net (code "31") (name "Net-(C212-Pad1)") (class "Default")
      (node (ref "C212") (pin "1") (pinfunction "1_1") (pintype "passive"))
      (node (ref "R121") (pin "2") (pinfunction "2_2") (pintype "passive"))
    )
    (net (code "32") (name "Net-(Q5-GATE)") (class "Default")
      (node (ref "Q5") (pin "1") (pinfunction "GATE_1") (pintype "passive"))
      (node (ref "Q8") (pin "3") (pinfunction "DRAIN_3") (pintype "passive"))
      (node (ref "R131") (pin "1") (pinfunction "1_1") (pintype "passive"))
    )
    (net (code "33") (name "Net-(U11-BOOT1)") (class "Default")
      (node (ref "R122") (pin "2") (pinfunction "2_2") (pintype "passive"))
      (node (ref "U11") (pin "17") (pinfunction "BOOT1_17") (pintype "passive"))
    )
    (net (code "34") (name "Net-(U11-BOOT2)") (class "Default")
      (node (ref "R121") (pin "1") (pinfunction "1_1") (pintype "passive"))
      (node (ref "U11") (pin "24") (pinfunction "BOOT2_24") (pintype "passive"))
    )
    (net (code "35") (name "Net-(U11-ILIM1)") (class "Default")
      (node (ref "R125") (pin "2") (pinfunction "2_2") (pintype "passive"))
      (node (ref "U11") (pin "12") (pinfunction "ILIM1_12") (pintype "passive"))
    )
    (net (code "36") (name "Net-(U11-ILIM2)") (class "Default")
      (node (ref "R124") (pin "1") (pinfunction "1_1") (pintype "passive"))
      (node (ref "U11") (pin "31") (pinfunction "ILIM2_31") (pintype "passive"))
    )
    (net (code "37") (name "Net-(U11-TON)") (class "Default")
      (node (ref "R128") (pin "1") (pinfunction "1_1") (pintype "passive"))
      (node (ref "R133") (pin "2") (pinfunction "2_2") (pintype "passive"))
      (node (ref "U11") (pin "2") (pinfunction "TON_2") (pintype "passive"))
    )
    (net (code "38") (name "Net-(U12-SLEEP)") (class "Default")
      (node (ref "R106") (pin "1") (pinfunction "1_1") (pintype "passive"))
      (node (ref "U12") (pin "8") (pinfunction "SLEEP_8") (pintype "passive"))
    )
    (net (code "39") (name "unconnected-(U11-BYP-Pad9)") (class "Default")
      (node (ref "U11") (pin "9") (pinfunction "BYP_9") (pintype "passive+no_connect"))
    )
  )
)
